# PSU_Board.net
KiCad netlist of a schematic drawn in EAGLE
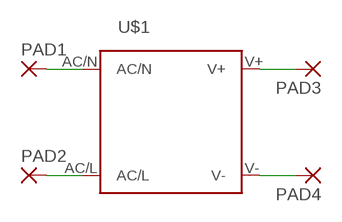
[diagram p0: schematic, sheet 1]

(export (version "E")
  (design (tool "Eeschema 10.0.6"))
  (components
    (comp (ref "PAD1")
      (value "3,81/1,4")
      (footprint "eagle-import:3,81_1,4")
      (libsource (lib "eagle-import") (part "3,81/1,4"))
    )
    (comp (ref "PAD2")
      (value "3,81/1,4")
      (footprint "eagle-import:3,81_1,4")
      (libsource (lib "eagle-import") (part "3,81/1,4"))
    )
    (comp (ref "PAD3")
      (value "3,81/1,4")
      (footprint "eagle-import:3,81_1,4")
      (libsource (lib "eagle-import") (part "3,81/1,4"))
    )
    (comp (ref "PAD4")
      (value "3,81/1,4")
      (footprint "eagle-import:3,81_1,4")
      (libsource (lib "eagle-import") (part "3,81/1,4"))
    )
    (comp (ref "U$1")
      (value "IRM_15/20")
      (footprint "eagle-import:IRM_15_20")
      (libsource (lib "eagle-import") (part "IRM_15/20"))
    )
  )
  (nets
    (net (code "1") (name "Net-(PAD1-P)") (class "Default")
      (node (ref "PAD1") (pin "1") (pinfunction "P_1") (pintype "passive"))
      (node (ref "U$1") (pin "AC/N") (pinfunction "AC/N_AC/N") (pintype "input"))
    )
    (net (code "2") (name "Net-(PAD2-P)") (class "Default")
      (node (ref "PAD2") (pin "1") (pinfunction "P_1") (pintype "passive"))
      (node (ref "U$1") (pin "AC/L") (pinfunction "AC/L_AC/L") (pintype "input"))
    )
    (net (code "3") (name "Net-(PAD3-P)") (class "Default")
      (node (ref "PAD3") (pin "1") (pinfunction "P_1") (pintype "passive"))
      (node (ref "U$1") (pin "V+") (pinfunction "V+_V+") (pintype "output"))
    )
    (net (code "4") (name "Net-(PAD4-P)") (class "Default")
      (node (ref "PAD4") (pin "1") (pinfunction "P_1") (pintype "passive"))
      (node (ref "U$1") (pin "V-") (pinfunction "V-_V-") (pintype "output"))
    )
  )
)
